# MotherBoard.net
KiCad netlist of a schematic drawn in Altium Designer
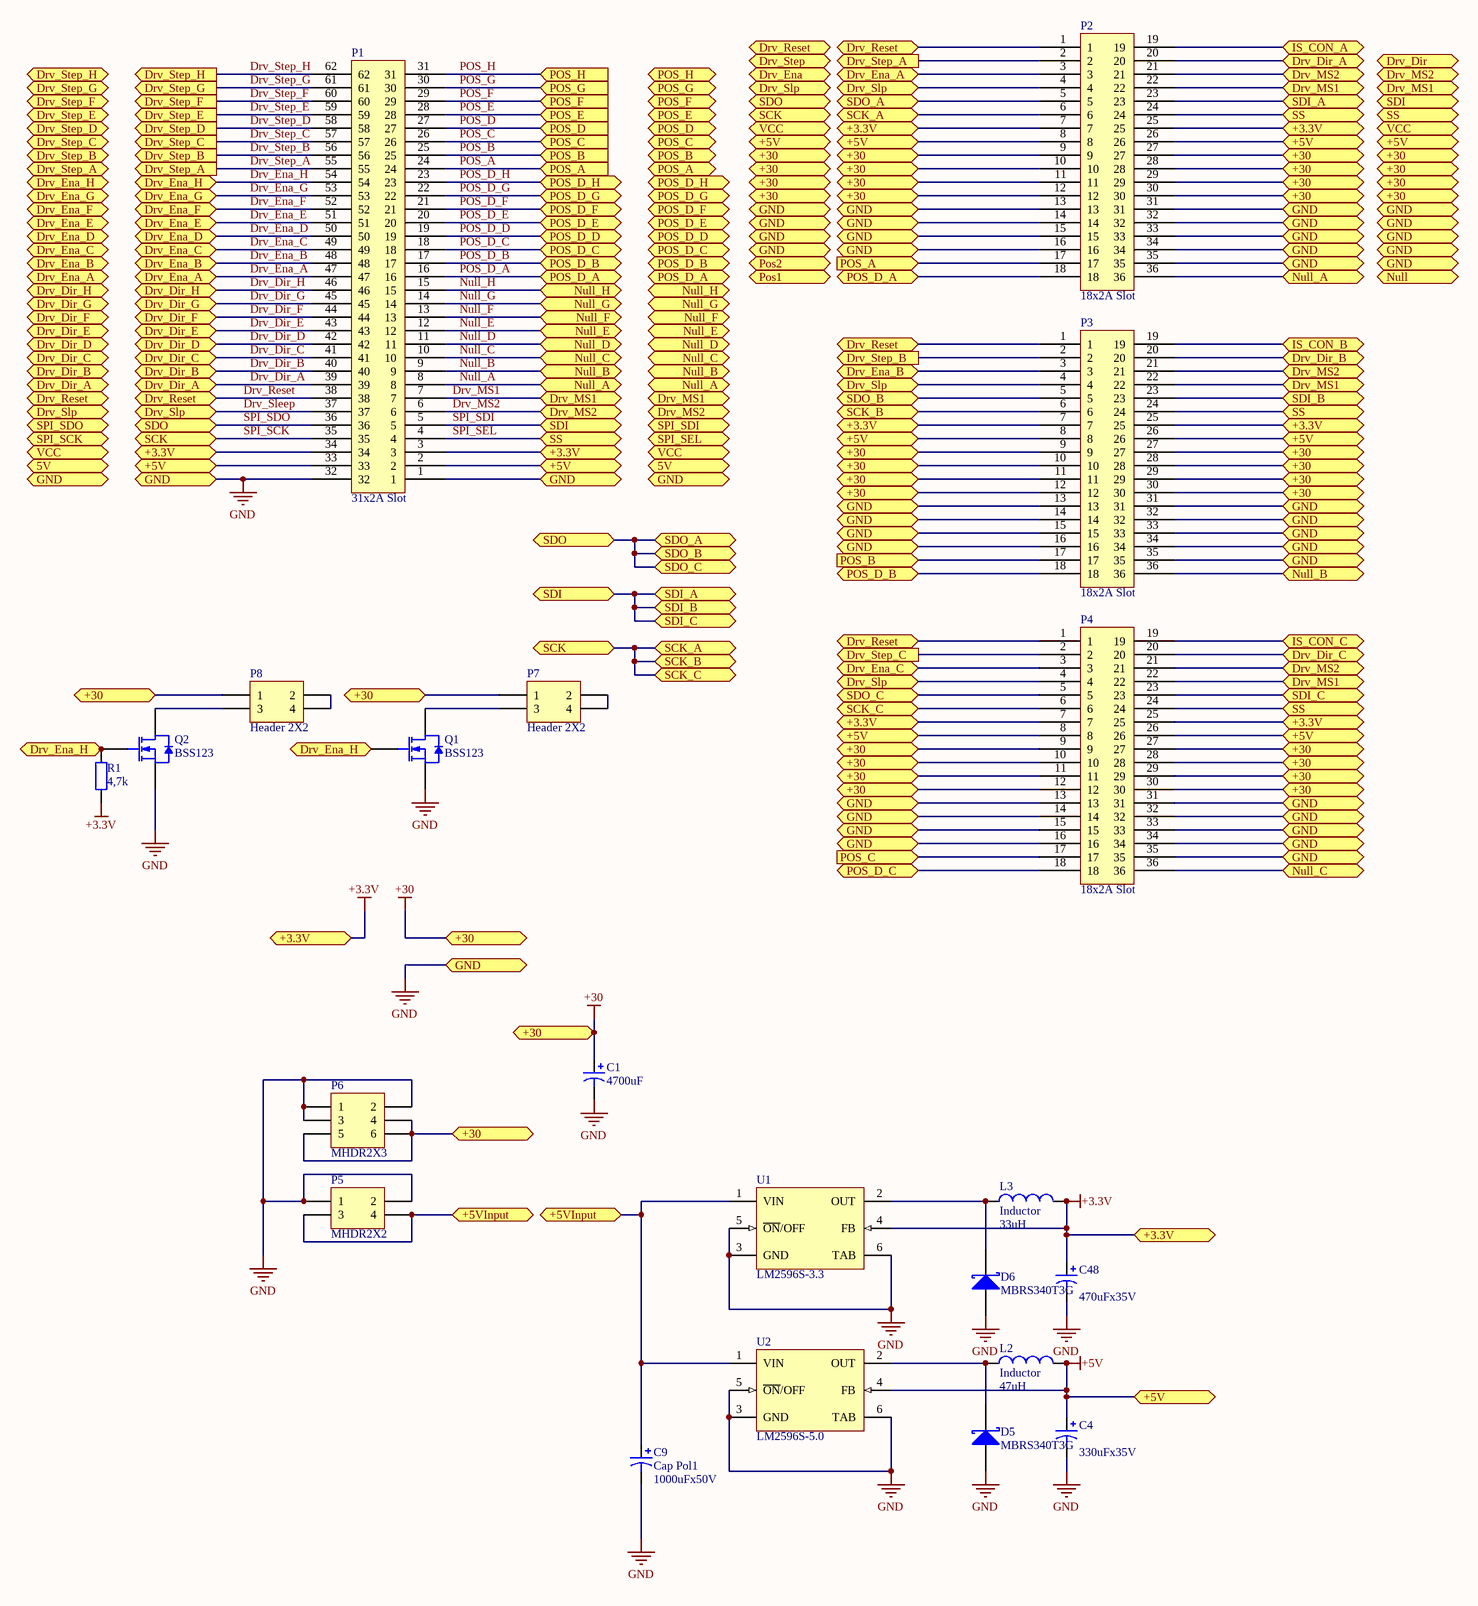
[diagram p0: MotherBoard.SchDoc]

(export (version "E")
  (design (tool "Eeschema 10.0.6"))
  (components
    (comp (ref "C1")
      (value "4700uF")
      (footprint "Cap16x36")
      (description "Polarized Capacitor (Radial)")
      (fields (field (name "Comment") "Cap Pol1") (field (name "PUBLISHER") "Altium Limited"))
      (libsource (lib "Miscellaneous Devices") (part "Cap Pol1"))
    )
    (comp (ref "C4")
      (value "330uFx35V")
      (footprint "Type E")
      (description "Polarized Capacitor (Radial)")
      (fields (field (name "Comment") "Cap Pol1") (field (name "PUBLISHER") "Altium Limited"))
      (libsource (lib "Miscellaneous Devices") (part "Cap Pol1"))
    )
    (comp (ref "C9")
      (value "Cap Pol1")
      (footprint "Cap13x25")
      (description "Polarized Capacitor (Radial)")
      (fields (field (name "ALTIUM_VALUE") "1000uFx50V") (field (name "PUBLISHER") "Altium Limited"))
      (libsource (lib "Miscellaneous Devices") (part "Cap Pol1"))
    )
    (comp (ref "C48")
      (value "470uFx35V")
      (footprint "Type E")
      (description "Polarized Capacitor (Radial)")
      (fields (field (name "Comment") "Cap Pol1") (field (name "PUBLISHER") "Altium Limited"))
      (libsource (lib "Miscellaneous Devices") (part "Cap Pol1"))
    )
    (comp (ref "D5")
      (value "MBRS340T3G")
      (footprint "SMC wbody")
      (description "Schottky Rectifier")
      (fields (field (name "PUBLISHER") "Altium Limited"))
      (libsource (lib "IR Rectifier - Schottky") (part "30BQ100"))
    )
    (comp (ref "D6")
      (value "MBRS340T3G")
      (footprint "SMC wbody")
      (description "Schottky Rectifier")
      (fields (field (name "PUBLISHER") "Altium Limited"))
      (libsource (lib "IR Rectifier - Schottky") (part "30BQ100"))
    )
    (comp (ref "L2")
      (value "Inductor")
      (footprint "CDRH127/LD")
      (fields (field (name "ALTIUM_VALUE") "47uH") (field (name "PUBLISHER") "Altium Limited"))
      (libsource (lib "Miscellaneous Devices") (part "Inductor"))
    )
    (comp (ref "L3")
      (value "Inductor")
      (footprint "CDRH127/LD")
      (fields (field (name "ALTIUM_VALUE") "33uH") (field (name "PUBLISHER") "Altium Limited"))
      (libsource (lib "Miscellaneous Devices") (part "Inductor"))
    )
    (comp (ref "P1")
      (value "31x2A Slot")
      (footprint "SL-62A")
      (description "31x2 Slot")
      (libsource (lib "Slot") (part "31x2A Slot"))
    )
    (comp (ref "P2") (value "18x2A Slot") (footprint "SL-36A") (libsource (lib "Slot") (part "18x2A Slot")))
    (comp (ref "P3") (value "18x2A Slot") (footprint "SL-36A") (libsource (lib "Slot") (part "18x2A Slot")))
    (comp (ref "P4") (value "18x2A Slot") (footprint "SL-36A") (libsource (lib "Slot") (part "18x2A Slot")))
    (comp (ref "P5")
      (value "MHDR2X2")
      (footprint "MF-2x2")
      (description "Header, 2-Pin, Dual row")
      (fields (field (name "PUBLISHER") "Altium Limited"))
      (libsource (lib "Miscellaneous Connectors") (part "MHDR2X2"))
    )
    (comp (ref "P6")
      (value "MHDR2X3")
      (footprint "MF-2x3")
      (description "Header, 3-Pin, Dual row")
      (fields (field (name "PUBLISHER") "Altium Limited"))
      (libsource (lib "Miscellaneous Connectors") (part "MHDR2X3"))
    )
    (comp (ref "P7")
      (value "Header 2X2")
      (footprint "HDR2X2")
      (description "Header, 2-Pin, Dual row")
      (fields (field (name "PUBLISHER") "Altium Limited"))
      (libsource (lib "Miscellaneous Connectors") (part "Header 2X2"))
    )
    (comp (ref "P8")
      (value "Header 2X2")
      (footprint "HDR2X2")
      (description "Header, 2-Pin, Dual row")
      (fields (field (name "PUBLISHER") "Altium Limited"))
      (libsource (lib "Miscellaneous Connectors") (part "Header 2X2"))
    )
    (comp (ref "Q1")
      (value "BSS123")
      (footprint "SOT23_N")
      (description "N-channel Enhancement Mode Vertical D-MOSFET")
      (fields (field (name "PUBLISHER") "Altium Limited"))
      (libsource (lib "Philips Discrete MOSFET - Low Power") (part "BSS123"))
    )
    (comp (ref "Q2")
      (value "BSS123")
      (footprint "SOT23_N")
      (description "N-channel Enhancement Mode Vertical D-MOSFET")
      (fields (field (name "PUBLISHER") "Altium Limited"))
      (libsource (lib "Philips Discrete MOSFET - Low Power") (part "BSS123"))
    )
    (comp (ref "R1")
      (value "4,7k")
      (footprint "RESC2012M")
      (description "Resistor")
      (fields (field (name "Comment") "Res2") (field (name "PUBLISHER") "Altium Limited"))
      (libsource (lib "Miscellaneous Devices") (part "Res2"))
    )
    (comp (ref "U1")
      (value "LM2596S-3.3")
      (footprint "TS5B_N")
      (description "SIMPLE SWITCHER Power Converter 150 KHz 3A Step-Down Voltage Regulator")
      (fields
        (field (name "MANUFACTURER") "National Semiconductor")
        (field (name "DIGIKEYPARTNUMBER") "LM2596S-3.3-ND")
        (field (name "PUBLISHER") "Altium Limited")
      )
      (libsource (lib "NSC Switcher") (part "LM2596S-3.3"))
    )
    (comp (ref "U2")
      (value "LM2596S-5.0")
      (footprint "TS5B_N")
      (description "SIMPLE SWITCHER Power Converter 150 KHz 3A Step-Down Voltage Regulator")
      (fields
        (field (name "MANUFACTURER") "National Semiconductor")
        (field (name "DIGIKEYPARTNUMBER") "LM2596S-5.0-ND")
        (field (name "PUBLISHER") "Altium Limited")
      )
      (libsource (lib "NSC Switcher") (part "LM2596S-5.0"))
    )
  )
  (nets
    (net (code "1") (name "+3.3V") (class "Default")
      (node (ref "C48") (pin "1") (pinfunction "1_1") (pintype "passive"))
      (node (ref "L3") (pin "2") (pinfunction "2_2") (pintype "passive"))
      (node (ref "P1") (pin "3") (pinfunction "3_3") (pintype "passive"))
      (node (ref "P1") (pin "34") (pinfunction "34_34") (pintype "passive"))
      (node (ref "P2") (pin "25") (pinfunction "25_25") (pintype "passive"))
      (node (ref "P2") (pin "7") (pinfunction "7_7") (pintype "passive"))
      (node (ref "P3") (pin "25") (pinfunction "25_25") (pintype "passive"))
      (node (ref "P3") (pin "7") (pinfunction "7_7") (pintype "passive"))
      (node (ref "P4") (pin "25") (pinfunction "25_25") (pintype "passive"))
      (node (ref "P4") (pin "7") (pinfunction "7_7") (pintype "passive"))
      (node (ref "R1") (pin "2") (pinfunction "2_2") (pintype "passive"))
      (node (ref "U1") (pin "4") (pinfunction "FB_4") (pintype "input"))
    )
    (net (code "2") (name "+5V") (class "Default")
      (node (ref "C4") (pin "1") (pinfunction "1_1") (pintype "passive"))
      (node (ref "L2") (pin "2") (pinfunction "2_2") (pintype "passive"))
      (node (ref "P1") (pin "2") (pinfunction "2_2") (pintype "passive"))
      (node (ref "P1") (pin "33") (pinfunction "33_33") (pintype "passive"))
      (node (ref "P2") (pin "26") (pinfunction "26_26") (pintype "passive"))
      (node (ref "P2") (pin "8") (pinfunction "8_8") (pintype "passive"))
      (node (ref "P3") (pin "26") (pinfunction "26_26") (pintype "passive"))
      (node (ref "P3") (pin "8") (pinfunction "8_8") (pintype "passive"))
      (node (ref "P4") (pin "26") (pinfunction "26_26") (pintype "passive"))
      (node (ref "P4") (pin "8") (pinfunction "8_8") (pintype "passive"))
      (node (ref "U2") (pin "4") (pinfunction "FB_4") (pintype "input"))
    )
    (net (code "3") (name "+30") (class "Default")
      (node (ref "C1") (pin "1") (pinfunction "1_1") (pintype "passive"))
      (node (ref "P2") (pin "10") (pinfunction "10_10") (pintype "passive"))
      (node (ref "P2") (pin "11") (pinfunction "11_11") (pintype "passive"))
      (node (ref "P2") (pin "12") (pinfunction "12_12") (pintype "passive"))
      (node (ref "P2") (pin "27") (pinfunction "27_27") (pintype "passive"))
      (node (ref "P2") (pin "28") (pinfunction "28_28") (pintype "passive"))
      (node (ref "P2") (pin "29") (pinfunction "29_29") (pintype "passive"))
      (node (ref "P2") (pin "30") (pinfunction "30_30") (pintype "passive"))
      (node (ref "P2") (pin "9") (pinfunction "9_9") (pintype "passive"))
      (node (ref "P3") (pin "10") (pinfunction "10_10") (pintype "passive"))
      (node (ref "P3") (pin "11") (pinfunction "11_11") (pintype "passive"))
      (node (ref "P3") (pin "12") (pinfunction "12_12") (pintype "passive"))
      (node (ref "P3") (pin "27") (pinfunction "27_27") (pintype "passive"))
      (node (ref "P3") (pin "28") (pinfunction "28_28") (pintype "passive"))
      (node (ref "P3") (pin "29") (pinfunction "29_29") (pintype "passive"))
      (node (ref "P3") (pin "30") (pinfunction "30_30") (pintype "passive"))
      (node (ref "P3") (pin "9") (pinfunction "9_9") (pintype "passive"))
      (node (ref "P4") (pin "10") (pinfunction "10_10") (pintype "passive"))
      (node (ref "P4") (pin "11") (pinfunction "11_11") (pintype "passive"))
      (node (ref "P4") (pin "12") (pinfunction "12_12") (pintype "passive"))
      (node (ref "P4") (pin "27") (pinfunction "27_27") (pintype "passive"))
      (node (ref "P4") (pin "28") (pinfunction "28_28") (pintype "passive"))
      (node (ref "P4") (pin "29") (pinfunction "29_29") (pintype "passive"))
      (node (ref "P4") (pin "30") (pinfunction "30_30") (pintype "passive"))
      (node (ref "P4") (pin "9") (pinfunction "9_9") (pintype "passive"))
      (node (ref "P6") (pin "4") (pinfunction "4_4") (pintype "passive"))
      (node (ref "P6") (pin "5") (pinfunction "5_5") (pintype "passive"))
      (node (ref "P6") (pin "6") (pinfunction "6_6") (pintype "passive"))
      (node (ref "P7") (pin "1") (pinfunction "1_1") (pintype "passive"))
      (node (ref "P8") (pin "1") (pinfunction "1_1") (pintype "passive"))
    )
    (net (code "4") (name "/+5VInput") (class "Default")
      (node (ref "C9") (pin "1") (pinfunction "1_1") (pintype "passive"))
      (node (ref "P5") (pin "3") (pinfunction "3_3") (pintype "passive"))
      (node (ref "P5") (pin "4") (pinfunction "4_4") (pintype "passive"))
      (node (ref "U1") (pin "1") (pinfunction "VIN_1") (pintype "power_in"))
      (node (ref "U2") (pin "1") (pinfunction "VIN_1") (pintype "power_in"))
    )
    (net (code "7") (name "/Drv_Dir_A") (class "Default")
      (node (ref "P1") (pin "39") (pinfunction "39_39") (pintype "passive"))
      (node (ref "P2") (pin "20") (pinfunction "20_20") (pintype "passive"))
    )
    (net (code "8") (name "/Drv_Dir_B") (class "Default")
      (node (ref "P1") (pin "40") (pinfunction "40_40") (pintype "passive"))
      (node (ref "P3") (pin "20") (pinfunction "20_20") (pintype "passive"))
    )
    (net (code "9") (name "/Drv_Dir_C") (class "Default")
      (node (ref "P1") (pin "41") (pinfunction "41_41") (pintype "passive"))
      (node (ref "P4") (pin "20") (pinfunction "20_20") (pintype "passive"))
    )
    (net (code "10") (name "/Drv_Dir_D") (class "Default")
      (node (ref "P1") (pin "42") (pinfunction "42_42") (pintype "passive"))
    )
    (net (code "11") (name "/Drv_Dir_E") (class "Default")
      (node (ref "P1") (pin "43") (pinfunction "43_43") (pintype "passive"))
    )
    (net (code "12") (name "/Drv_Dir_F") (class "Default")
      (node (ref "P1") (pin "44") (pinfunction "44_44") (pintype "passive"))
    )
    (net (code "13") (name "/Drv_Dir_G") (class "Default")
      (node (ref "P1") (pin "45") (pinfunction "45_45") (pintype "passive"))
    )
    (net (code "14") (name "/Drv_Dir_H") (class "Default")
      (node (ref "P1") (pin "46") (pinfunction "46_46") (pintype "passive"))
    )
    (net (code "16") (name "/Drv_Ena_A") (class "Default")
      (node (ref "P1") (pin "47") (pinfunction "47_47") (pintype "passive"))
      (node (ref "P2") (pin "3") (pinfunction "3_3") (pintype "passive"))
    )
    (net (code "17") (name "/Drv_Ena_B") (class "Default")
      (node (ref "P1") (pin "48") (pinfunction "48_48") (pintype "passive"))
      (node (ref "P3") (pin "3") (pinfunction "3_3") (pintype "passive"))
    )
    (net (code "18") (name "/Drv_Ena_C") (class "Default")
      (node (ref "P1") (pin "49") (pinfunction "49_49") (pintype "passive"))
      (node (ref "P4") (pin "3") (pinfunction "3_3") (pintype "passive"))
    )
    (net (code "19") (name "/Drv_Ena_D") (class "Default")
      (node (ref "P1") (pin "50") (pinfunction "50_50") (pintype "passive"))
    )
    (net (code "20") (name "/Drv_Ena_E") (class "Default")
      (node (ref "P1") (pin "51") (pinfunction "51_51") (pintype "passive"))
    )
    (net (code "21") (name "/Drv_Ena_F") (class "Default")
      (node (ref "P1") (pin "52") (pinfunction "52_52") (pintype "passive"))
    )
    (net (code "22") (name "/Drv_Ena_G") (class "Default")
      (node (ref "P1") (pin "53") (pinfunction "53_53") (pintype "passive"))
    )
    (net (code "23") (name "/Drv_Ena_H") (class "Default")
      (node (ref "P1") (pin "54") (pinfunction "54_54") (pintype "passive"))
      (node (ref "Q1") (pin "1") (pinfunction "G_1") (pintype "passive"))
      (node (ref "Q2") (pin "1") (pinfunction "G_1") (pintype "passive"))
      (node (ref "R1") (pin "1") (pinfunction "1_1") (pintype "passive"))
    )
    (net (code "24") (name "/Drv_MS1") (class "Default")
      (node (ref "P1") (pin "7") (pinfunction "7_7") (pintype "passive"))
      (node (ref "P2") (pin "22") (pinfunction "22_22") (pintype "passive"))
      (node (ref "P3") (pin "22") (pinfunction "22_22") (pintype "passive"))
      (node (ref "P4") (pin "22") (pinfunction "22_22") (pintype "passive"))
    )
    (net (code "25") (name "/Drv_MS2") (class "Default")
      (node (ref "P1") (pin "6") (pinfunction "6_6") (pintype "passive"))
      (node (ref "P2") (pin "21") (pinfunction "21_21") (pintype "passive"))
      (node (ref "P3") (pin "21") (pinfunction "21_21") (pintype "passive"))
      (node (ref "P4") (pin "21") (pinfunction "21_21") (pintype "passive"))
    )
    (net (code "26") (name "/Drv_Reset") (class "Default")
      (node (ref "P1") (pin "38") (pinfunction "38_38") (pintype "passive"))
      (node (ref "P2") (pin "1") (pinfunction "1_1") (pintype "passive"))
      (node (ref "P3") (pin "1") (pinfunction "1_1") (pintype "passive"))
      (node (ref "P4") (pin "1") (pinfunction "1_1") (pintype "passive"))
    )
    (net (code "27") (name "/Drv_Sleep") (class "Default")
      (node (ref "P1") (pin "37") (pinfunction "37_37") (pintype "passive"))
      (node (ref "P2") (pin "4") (pinfunction "4_4") (pintype "passive"))
      (node (ref "P3") (pin "4") (pinfunction "4_4") (pintype "passive"))
      (node (ref "P4") (pin "4") (pinfunction "4_4") (pintype "passive"))
    )
    (net (code "29") (name "/Drv_Step_A") (class "Default")
      (node (ref "P1") (pin "55") (pinfunction "55_55") (pintype "passive"))
      (node (ref "P2") (pin "2") (pinfunction "2_2") (pintype "passive"))
    )
    (net (code "30") (name "/Drv_Step_B") (class "Default")
      (node (ref "P1") (pin "56") (pinfunction "56_56") (pintype "passive"))
      (node (ref "P3") (pin "2") (pinfunction "2_2") (pintype "passive"))
    )
    (net (code "31") (name "/Drv_Step_C") (class "Default")
      (node (ref "P1") (pin "57") (pinfunction "57_57") (pintype "passive"))
      (node (ref "P4") (pin "2") (pinfunction "2_2") (pintype "passive"))
    )
    (net (code "32") (name "/Drv_Step_D") (class "Default")
      (node (ref "P1") (pin "58") (pinfunction "58_58") (pintype "passive"))
    )
    (net (code "33") (name "/Drv_Step_E") (class "Default")
      (node (ref "P1") (pin "59") (pinfunction "59_59") (pintype "passive"))
    )
    (net (code "34") (name "/Drv_Step_F") (class "Default")
      (node (ref "P1") (pin "60") (pinfunction "60_60") (pintype "passive"))
    )
    (net (code "35") (name "/Drv_Step_G") (class "Default")
      (node (ref "P1") (pin "61") (pinfunction "61_61") (pintype "passive"))
    )
    (net (code "36") (name "/Drv_Step_H") (class "Default")
      (node (ref "P1") (pin "62") (pinfunction "62_62") (pintype "passive"))
    )
    (net (code "37") (name "/IS_CON_A") (class "Default")
      (node (ref "P2") (pin "19") (pinfunction "19_19") (pintype "passive"))
    )
    (net (code "38") (name "/IS_CON_B") (class "Default")
      (node (ref "P3") (pin "19") (pinfunction "19_19") (pintype "passive"))
    )
    (net (code "39") (name "/IS_CON_C") (class "Default")
      (node (ref "P4") (pin "19") (pinfunction "19_19") (pintype "passive"))
    )
    (net (code "41") (name "/Null_A") (class "Default")
      (node (ref "P1") (pin "8") (pinfunction "8_8") (pintype "passive"))
      (node (ref "P2") (pin "36") (pinfunction "36_36") (pintype "passive"))
    )
    (net (code "42") (name "/Null_B") (class "Default")
      (node (ref "P1") (pin "9") (pinfunction "9_9") (pintype "passive"))
      (node (ref "P3") (pin "36") (pinfunction "36_36") (pintype "passive"))
    )
    (net (code "43") (name "/Null_C") (class "Default")
      (node (ref "P1") (pin "10") (pinfunction "10_10") (pintype "passive"))
      (node (ref "P4") (pin "36") (pinfunction "36_36") (pintype "passive"))
    )
    (net (code "44") (name "/Null_D") (class "Default")
      (node (ref "P1") (pin "11") (pinfunction "11_11") (pintype "passive"))
    )
    (net (code "45") (name "/Null_E") (class "Default")
      (node (ref "P1") (pin "12") (pinfunction "12_12") (pintype "passive"))
    )
    (net (code "46") (name "/Null_F") (class "Default")
      (node (ref "P1") (pin "13") (pinfunction "13_13") (pintype "passive"))
    )
    (net (code "47") (name "/Null_G") (class "Default")
      (node (ref "P1") (pin "14") (pinfunction "14_14") (pintype "passive"))
    )
    (net (code "48") (name "/Null_H") (class "Default")
      (node (ref "P1") (pin "15") (pinfunction "15_15") (pintype "passive"))
    )
    (net (code "49") (name "/POS_A") (class "Default")
      (node (ref "P1") (pin "24") (pinfunction "24_24") (pintype "passive"))
      (node (ref "P2") (pin "17") (pinfunction "17_17") (pintype "passive"))
    )
    (net (code "50") (name "/POS_B") (class "Default")
      (node (ref "P1") (pin "25") (pinfunction "25_25") (pintype "passive"))
      (node (ref "P3") (pin "17") (pinfunction "17_17") (pintype "passive"))
    )
    (net (code "51") (name "/POS_C") (class "Default")
      (node (ref "P1") (pin "26") (pinfunction "26_26") (pintype "passive"))
      (node (ref "P4") (pin "17") (pinfunction "17_17") (pintype "passive"))
    )
    (net (code "52") (name "/POS_D") (class "Default")
      (node (ref "P1") (pin "27") (pinfunction "27_27") (pintype "passive"))
    )
    (net (code "53") (name "/POS_D_A") (class "Default")
      (node (ref "P1") (pin "16") (pinfunction "16_16") (pintype "passive"))
      (node (ref "P2") (pin "18") (pinfunction "18_18") (pintype "passive"))
    )
    (net (code "54") (name "/POS_D_B") (class "Default")
      (node (ref "P1") (pin "17") (pinfunction "17_17") (pintype "passive"))
      (node (ref "P3") (pin "18") (pinfunction "18_18") (pintype "passive"))
    )
    (net (code "55") (name "/POS_D_C") (class "Default")
      (node (ref "P1") (pin "18") (pinfunction "18_18") (pintype "passive"))
      (node (ref "P4") (pin "18") (pinfunction "18_18") (pintype "passive"))
    )
    (net (code "56") (name "/POS_D_D") (class "Default")
      (node (ref "P1") (pin "19") (pinfunction "19_19") (pintype "passive"))
    )
    (net (code "57") (name "/POS_D_E") (class "Default")
      (node (ref "P1") (pin "20") (pinfunction "20_20") (pintype "passive"))
    )
    (net (code "58") (name "/POS_D_F") (class "Default")
      (node (ref "P1") (pin "21") (pinfunction "21_21") (pintype "passive"))
    )
    (net (code "59") (name "/POS_D_G") (class "Default")
      (node (ref "P1") (pin "22") (pinfunction "22_22") (pintype "passive"))
    )
    (net (code "60") (name "/POS_D_H") (class "Default")
      (node (ref "P1") (pin "23") (pinfunction "23_23") (pintype "passive"))
    )
    (net (code "61") (name "/POS_E") (class "Default")
      (node (ref "P1") (pin "28") (pinfunction "28_28") (pintype "passive"))
    )
    (net (code "62") (name "/POS_F") (class "Default")
      (node (ref "P1") (pin "29") (pinfunction "29_29") (pintype "passive"))
    )
    (net (code "63") (name "/POS_G") (class "Default")
      (node (ref "P1") (pin "30") (pinfunction "30_30") (pintype "passive"))
    )
    (net (code "64") (name "/POS_H") (class "Default")
      (node (ref "P1") (pin "31") (pinfunction "31_31") (pintype "passive"))
    )
    (net (code "67") (name "/SPI_SCK") (class "Default")
      (node (ref "P1") (pin "35") (pinfunction "35_35") (pintype "passive"))
      (node (ref "P2") (pin "6") (pinfunction "6_6") (pintype "passive"))
      (node (ref "P3") (pin "6") (pinfunction "6_6") (pintype "passive"))
      (node (ref "P4") (pin "6") (pinfunction "6_6") (pintype "passive"))
    )
    (net (code "68") (name "/SPI_SDI") (class "Default")
      (node (ref "P1") (pin "5") (pinfunction "5_5") (pintype "passive"))
      (node (ref "P2") (pin "23") (pinfunction "23_23") (pintype "passive"))
      (node (ref "P3") (pin "23") (pinfunction "23_23") (pintype "passive"))
      (node (ref "P4") (pin "23") (pinfunction "23_23") (pintype "passive"))
    )
    (net (code "69") (name "/SPI_SDO") (class "Default")
      (node (ref "P1") (pin "36") (pinfunction "36_36") (pintype "passive"))
      (node (ref "P2") (pin "5") (pinfunction "5_5") (pintype "passive"))
      (node (ref "P3") (pin "5") (pinfunction "5_5") (pintype "passive"))
      (node (ref "P4") (pin "5") (pinfunction "5_5") (pintype "passive"))
    )
    (net (code "70") (name "/SPI_SEL") (class "Default")
      (node (ref "P1") (pin "4") (pinfunction "4_4") (pintype "passive"))
      (node (ref "P2") (pin "24") (pinfunction "24_24") (pintype "passive"))
      (node (ref "P3") (pin "24") (pinfunction "24_24") (pintype "passive"))
      (node (ref "P4") (pin "24") (pinfunction "24_24") (pintype "passive"))
    )
    (net (code "72") (name "GND") (class "Default")
      (node (ref "C1") (pin "2") (pinfunction "2_2") (pintype "passive"))
      (node (ref "C4") (pin "2") (pinfunction "2_2") (pintype "passive"))
      (node (ref "C48") (pin "2") (pinfunction "2_2") (pintype "passive"))
      (node (ref "C9") (pin "2") (pinfunction "2_2") (pintype "passive"))
      (node (ref "D5") (pin "1") (pinfunction "A_1") (pintype "passive"))
      (node (ref "D6") (pin "1") (pinfunction "A_1") (pintype "passive"))
      (node (ref "P1") (pin "1") (pinfunction "1_1") (pintype "passive"))
      (node (ref "P1") (pin "32") (pinfunction "32_32") (pintype "passive"))
      (node (ref "P2") (pin "13") (pinfunction "13_13") (pintype "passive"))
      (node (ref "P2") (pin "14") (pinfunction "14_14") (pintype "passive"))
      (node (ref "P2") (pin "15") (pinfunction "15_15") (pintype "passive"))
      (node (ref "P2") (pin "16") (pinfunction "16_16") (pintype "passive"))
      (node (ref "P2") (pin "31") (pinfunction "31_31") (pintype "passive"))
      (node (ref "P2") (pin "32") (pinfunction "32_32") (pintype "passive"))
      (node (ref "P2") (pin "33") (pinfunction "33_33") (pintype "passive"))
      (node (ref "P2") (pin "34") (pinfunction "34_34") (pintype "passive"))
      (node (ref "P2") (pin "35") (pinfunction "35_35") (pintype "passive"))
      (node (ref "P3") (pin "13") (pinfunction "13_13") (pintype "passive"))
      (node (ref "P3") (pin "14") (pinfunction "14_14") (pintype "passive"))
      (node (ref "P3") (pin "15") (pinfunction "15_15") (pintype "passive"))
      (node (ref "P3") (pin "16") (pinfunction "16_16") (pintype "passive"))
      (node (ref "P3") (pin "31") (pinfunction "31_31") (pintype "passive"))
      (node (ref "P3") (pin "32") (pinfunction "32_32") (pintype "passive"))
      (node (ref "P3") (pin "33") (pinfunction "33_33") (pintype "passive"))
      (node (ref "P3") (pin "34") (pinfunction "34_34") (pintype "passive"))
      (node (ref "P3") (pin "35") (pinfunction "35_35") (pintype "passive"))
      (node (ref "P4") (pin "13") (pinfunction "13_13") (pintype "passive"))
      (node (ref "P4") (pin "14") (pinfunction "14_14") (pintype "passive"))
      (node (ref "P4") (pin "15") (pinfunction "15_15") (pintype "passive"))
      (node (ref "P4") (pin "16") (pinfunction "16_16") (pintype "passive"))
      (node (ref "P4") (pin "31") (pinfunction "31_31") (pintype "passive"))
      (node (ref "P4") (pin "32") (pinfunction "32_32") (pintype "passive"))
      (node (ref "P4") (pin "33") (pinfunction "33_33") (pintype "passive"))
      (node (ref "P4") (pin "34") (pinfunction "34_34") (pintype "passive"))
      (node (ref "P4") (pin "35") (pinfunction "35_35") (pintype "passive"))
      (node (ref "P5") (pin "1") (pinfunction "1_1") (pintype "passive"))
      (node (ref "P5") (pin "2") (pinfunction "2_2") (pintype "passive"))
      (node (ref "P6") (pin "1") (pinfunction "1_1") (pintype "passive"))
      (node (ref "P6") (pin "2") (pinfunction "2_2") (pintype "passive"))
      (node (ref "P6") (pin "3") (pinfunction "3_3") (pintype "passive"))
      (node (ref "Q1") (pin "2") (pinfunction "S_2") (pintype "passive"))
      (node (ref "Q2") (pin "2") (pinfunction "S_2") (pintype "passive"))
      (node (ref "U1") (pin "3") (pinfunction "GND_3") (pintype "power_in"))
      (node (ref "U1") (pin "5") (pinfunction "~{ON}/OFF_5") (pintype "input"))
      (node (ref "U1") (pin "6") (pinfunction "TAB_6") (pintype "power_in"))
      (node (ref "U2") (pin "3") (pinfunction "GND_3") (pintype "power_in"))
      (node (ref "U2") (pin "5") (pinfunction "~{ON}/OFF_5") (pintype "input"))
      (node (ref "U2") (pin "6") (pinfunction "TAB_6") (pintype "power_in"))
    )
    (net (code "73") (name "Net-(D5-K)") (class "Default")
      (node (ref "D5") (pin "2") (pinfunction "K_2") (pintype "passive"))
      (node (ref "L2") (pin "1") (pinfunction "1_1") (pintype "passive"))
      (node (ref "U2") (pin "2") (pinfunction "OUT_2") (pintype "power_in"))
    )
    (net (code "74") (name "Net-(D6-K)") (class "Default")
      (node (ref "D6") (pin "2") (pinfunction "K_2") (pintype "passive"))
      (node (ref "L3") (pin "1") (pinfunction "1_1") (pintype "passive"))
      (node (ref "U1") (pin "2") (pinfunction "OUT_2") (pintype "power_in"))
    )
    (net (code "75") (name "Net-(P7-Pad2)") (class "Default")
      (node (ref "P7") (pin "2") (pinfunction "2_2") (pintype "passive"))
      (node (ref "P7") (pin "4") (pinfunction "4_4") (pintype "passive"))
    )
    (net (code "76") (name "Net-(P8-Pad2)") (class "Default")
      (node (ref "P8") (pin "2") (pinfunction "2_2") (pintype "passive"))
      (node (ref "P8") (pin "4") (pinfunction "4_4") (pintype "passive"))
    )
    (net (code "77") (name "Net-(Q1-D)") (class "Default")
      (node (ref "P7") (pin "3") (pinfunction "3_3") (pintype "passive"))
      (node (ref "Q1") (pin "3") (pinfunction "D_3") (pintype "passive"))
    )
    (net (code "78") (name "Net-(Q2-D)") (class "Default")
      (node (ref "P8") (pin "3") (pinfunction "3_3") (pintype "passive"))
      (node (ref "Q2") (pin "3") (pinfunction "D_3") (pintype "passive"))
    )
  )
)
